# Fuente_Conn.net
KiCad netlist of a schematic drawn in Altium Designer
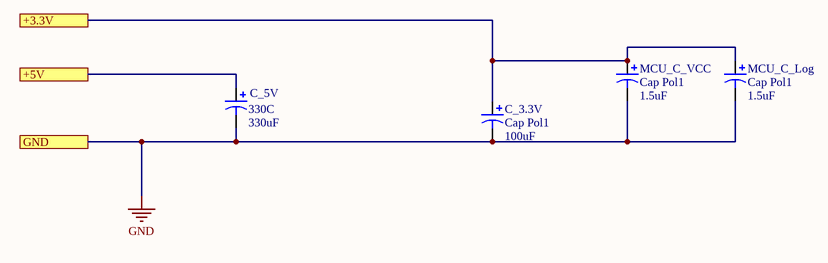
[diagram p0: Fuente_Conn.SchDoc]

(export (version "E")
  (design (tool "Eeschema 10.0.6"))
  (components
    (comp (ref "C_3.3V")
      (value "Cap Pol1")
      (footprint "Capacitor S Panasonic")
      (description "Polarized Capacitor (Radial)")
      (fields (field (name "ALTIUM_VALUE") "100uF") (field (name "PUBLISHER") "Altium Limited"))
      (libsource (lib "Miscellaneous Devices") (part "Cap Pol1"))
    )
    (comp (ref "C_5V")
      (value "330C")
      (footprint "PANASONIC_C")
      (description "Polarized Capacitor (Radial)")
      (fields (field (name "ALTIUM_VALUE") "330uF") (field (name "PUBLISHER") "Altium Limited"))
      (libsource (lib "Miscellaneous Devices") (part "Cap Pol1"))
    )
    (comp (ref "MCU_C_Log")
      (value "Cap Pol1")
      (footprint "6-0805_L")
      (description "Polarized Capacitor (Radial)")
      (fields (field (name "ALTIUM_VALUE") "1.5uF") (field (name "PUBLISHER") "Altium Limited"))
      (libsource (lib "Miscellaneous Devices") (part "Cap Pol1"))
    )
    (comp (ref "MCU_C_VCC")
      (value "Cap Pol1")
      (footprint "6-0805_L")
      (description "Polarized Capacitor (Radial)")
      (fields (field (name "ALTIUM_VALUE") "1.5uF") (field (name "PUBLISHER") "Altium Limited"))
      (libsource (lib "Miscellaneous Devices") (part "Cap Pol1"))
    )
  )
  (nets
    (net (code "1") (name "/+3.3V") (class "Default")
      (node (ref "C_3.3V") (pin "1") (pinfunction "1_1") (pintype "passive"))
      (node (ref "MCU_C_Log") (pin "1") (pinfunction "1_1") (pintype "passive"))
      (node (ref "MCU_C_VCC") (pin "1") (pinfunction "1_1") (pintype "passive"))
    )
    (net (code "2") (name "/+5V") (class "Default")
      (node (ref "C_5V") (pin "1") (pinfunction "1_1") (pintype "passive"))
    )
    (net (code "3") (name "GND") (class "Default")
      (node (ref "C_3.3V") (pin "2") (pinfunction "2_2") (pintype "passive"))
      (node (ref "C_5V") (pin "2") (pinfunction "2_2") (pintype "passive"))
      (node (ref "MCU_C_Log") (pin "2") (pinfunction "2_2") (pintype "passive"))
      (node (ref "MCU_C_VCC") (pin "2") (pinfunction "2_2") (pintype "passive"))
    )
  )
)
